# FRAM.net
KiCad netlist of a schematic drawn in Altium Designer
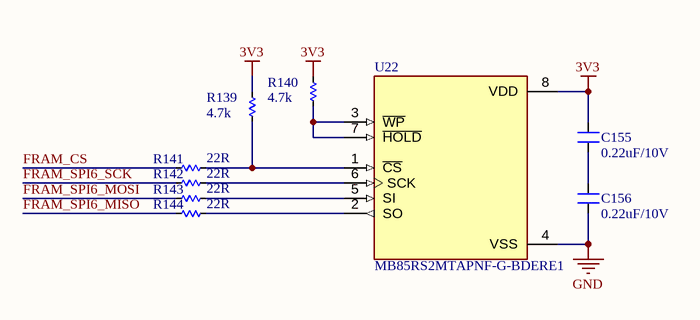
[diagram p0: FRAM.SchDoc]

(export (version "E")
  (design (tool "Eeschema 10.0.6"))
  (components
    (comp (ref "C155")
      (value "0.22uF/10V")
      (footprint "CAP_C_1608X80")
      (libsource (lib "EXP_HW_V3") (part "Capacitors"))
    )
    (comp (ref "C156")
      (value "0.22uF/10V")
      (footprint "CAP_C_1608X80")
      (libsource (lib "EXP_HW_V3") (part "Capacitors"))
    )
    (comp (ref "R139")
      (value "4.7k")
      (footprint "RES_C_1608X60")
      (description "SMD")
      (fields
        (field (name "MANUFACTURER") "Generic Components")
        (field (name "PUBLISHER") "Altium Hobart Technology Centre")
      )
      (libsource (lib "EXP_HW_V3") (part "Res SMD"))
    )
    (comp (ref "R140")
      (value "4.7k")
      (footprint "RES_C_1608X60")
      (description "SMD")
      (fields
        (field (name "MANUFACTURER") "Generic Components")
        (field (name "PUBLISHER") "Altium Hobart Technology Centre")
      )
      (libsource (lib "EXP_HW_V3") (part "Res SMD"))
    )
    (comp (ref "R141")
      (value "22R")
      (footprint "RES_C_1608X60")
      (description "SMD")
      (fields
        (field (name "MANUFACTURER") "Generic Components")
        (field (name "PUBLISHER") "Altium Hobart Technology Centre")
      )
      (libsource (lib "EXP_HW_V3") (part "Res SMD"))
    )
    (comp (ref "R142")
      (value "22R")
      (footprint "RES_C_1608X60")
      (description "SMD")
      (fields
        (field (name "MANUFACTURER") "Generic Components")
        (field (name "PUBLISHER") "Altium Hobart Technology Centre")
      )
      (libsource (lib "EXP_HW_V3") (part "Res SMD"))
    )
    (comp (ref "R143")
      (value "22R")
      (footprint "RES_C_1608X60")
      (description "SMD")
      (fields
        (field (name "MANUFACTURER") "Generic Components")
        (field (name "PUBLISHER") "Altium Hobart Technology Centre")
      )
      (libsource (lib "EXP_HW_V3") (part "Res SMD"))
    )
    (comp (ref "R144")
      (value "22R")
      (footprint "RES_C_1608X60")
      (description "SMD")
      (fields
        (field (name "MANUFACTURER") "Generic Components")
        (field (name "PUBLISHER") "Altium Hobart Technology Centre")
      )
      (libsource (lib "EXP_HW_V3") (part "Res SMD"))
    )
    (comp (ref "U22")
      (value "MB85RS2MTAPNF-G-BDERE1")
      (footprint "MB85RS2MTAPNF-G-BDERE1")
      (description "FRAM _Ferroelectric RAM_ Memory IC 2Mb _256K x 8_ SPI 40MHz 8-SOP")
      (fields (field (name "MF") "Fujitsu Electronics") (field (name "DIGI-KEY_PART_NUMBER") "865-1286-1-ND"))
      (libsource (lib "EXP_HW_V3") (part "MB85RS2MTAPNF-G-BDERE1"))
    )
  )
  (nets
    (net (code "1") (name "/FRAM_CS") (class "Default")
      (node (ref "R141") (pin "1") (pinfunction "1_1") (pintype "passive"))
    )
    (net (code "2") (name "/FRAM_SPI6_MISO") (class "Default")
      (node (ref "R144") (pin "1") (pinfunction "1_1") (pintype "passive"))
    )
    (net (code "3") (name "/FRAM_SPI6_MOSI") (class "Default")
      (node (ref "R143") (pin "1") (pinfunction "1_1") (pintype "passive"))
    )
    (net (code "4") (name "/FRAM_SPI6_SCK") (class "Default")
      (node (ref "R142") (pin "1") (pinfunction "1_1") (pintype "passive"))
    )
    (net (code "5") (name "3V3") (class "Default")
      (node (ref "C155") (pin "2") (pinfunction "2_2") (pintype "passive"))
      (node (ref "R139") (pin "1") (pinfunction "1_1") (pintype "passive"))
      (node (ref "R140") (pin "1") (pinfunction "1_1") (pintype "passive"))
      (node (ref "U22") (pin "8") (pinfunction "VDD_8") (pintype "power_in"))
    )
    (net (code "6") (name "GND") (class "Default")
      (node (ref "C156") (pin "1") (pinfunction "1_1") (pintype "passive"))
      (node (ref "U22") (pin "4") (pinfunction "VSS_4") (pintype "power_in"))
    )
    (net (code "7") (name "Net-(C155-Pad1)") (class "Default")
      (node (ref "C155") (pin "1") (pinfunction "1_1") (pintype "passive"))
      (node (ref "C156") (pin "2") (pinfunction "2_2") (pintype "passive"))
    )
    (net (code "8") (name "Net-(U22-SCK)") (class "Default")
      (node (ref "R142") (pin "2") (pinfunction "2_2") (pintype "passive"))
      (node (ref "U22") (pin "6") (pinfunction "SCK_6") (pintype "input"))
    )
    (net (code "9") (name "Net-(U22-SI)") (class "Default")
      (node (ref "R143") (pin "2") (pinfunction "2_2") (pintype "passive"))
      (node (ref "U22") (pin "5") (pinfunction "SI_5") (pintype "input"))
    )
    (net (code "10") (name "Net-(U22-SO)") (class "Default")
      (node (ref "R144") (pin "2") (pinfunction "2_2") (pintype "passive"))
      (node (ref "U22") (pin "2") (pinfunction "SO_2") (pintype "output"))
    )
    (net (code "11") (name "Net-(U22-~{CS})") (class "Default")
      (node (ref "R139") (pin "2") (pinfunction "2_2") (pintype "passive"))
      (node (ref "R141") (pin "2") (pinfunction "2_2") (pintype "passive"))
      (node (ref "U22") (pin "1") (pinfunction "~{CS}_1") (pintype "input"))
    )
    (net (code "12") (name "Net-(U22-~{HOLD})") (class "Default")
      (node (ref "R140") (pin "2") (pinfunction "2_2") (pintype "passive"))
      (node (ref "U22") (pin "3") (pinfunction "~{WP}_3") (pintype "input"))
      (node (ref "U22") (pin "7") (pinfunction "~{HOLD}_7") (pintype "input"))
    )
  )
)
